# raspi_active_cooling.net
KiCad netlist of a schematic drawn in EAGLE
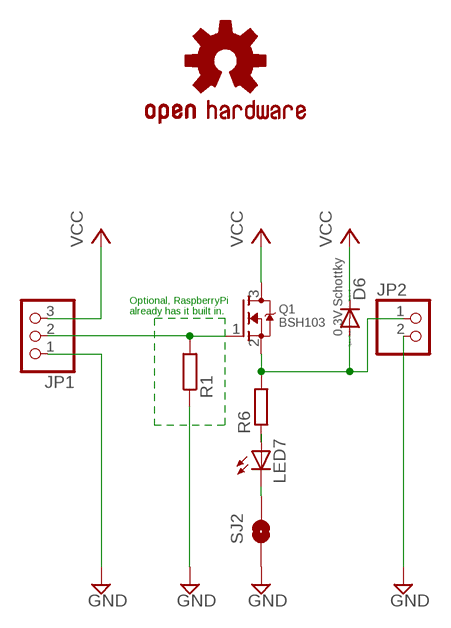
[diagram p0: schematic, sheet 1]

(export (version "E")
  (design (tool "Eeschema 10.0.6"))
  (components
    (comp (ref "D6")
      (value "0.3V Schottky")
      (footprint "eagle-import:SOD523")
      (libsource (lib "eagle-import") (part "DIODE-SOD523"))
    )
    (comp (ref "JP1")
      (value "PINHD-1X3/90")
      (footprint "eagle-import:1X03_90")
      (libsource (lib "eagle-import") (part "PINHD-1X3/90"))
    )
    (comp (ref "JP2")
      (value "PINHD-1X2/90")
      (footprint "eagle-import:1X02_90")
      (libsource (lib "eagle-import") (part "PINHD-1X2/90"))
    )
    (comp (ref "LED7")
      (value "LED0603")
      (footprint "eagle-import:LED-0603")
      (libsource (lib "eagle-import") (part "LED0603"))
    )
    (comp (ref "LOGO1")
      (value "OSHW-LOGOS")
      (footprint "eagle-import:OSHW-LOGO-S")
      (libsource (lib "eagle-import") (part "OSHW-LOGOS"))
    )
    (comp (ref "Q1")
      (value "BSH103")
      (footprint "eagle-import:SOT23")
      (libsource (lib "eagle-import") (part "MOSFET-NREFLOW"))
    )
    (comp (ref "R1")
      (value "R-EU_R0603")
      (footprint "eagle-import:R0603")
      (libsource (lib "eagle-import") (part "R-EU_R0603"))
    )
    (comp (ref "R6")
      (value "R-EU_R0603")
      (footprint "eagle-import:R0603")
      (libsource (lib "eagle-import") (part "R-EU_R0603"))
    )
    (comp (ref "SJ2")
      (value "SOLDERJUMPERNO")
      (footprint "eagle-import:SJ_2S-NO")
      (libsource (lib "eagle-import") (part "SOLDERJUMPERNO"))
    )
  )
  (nets
    (net (code "1") (name "GND") (class "Default")
      (node (ref "JP1") (pin "1") (pinfunction "1_1") (pintype "passive"))
      (node (ref "JP2") (pin "2") (pinfunction "2_2") (pintype "passive"))
      (node (ref "R1") (pin "1") (pinfunction "1_1") (pintype "passive"))
      (node (ref "SJ2") (pin "2") (pinfunction "2_2") (pintype "passive"))
    )
    (net (code "2") (name "Net-(LED7-PadA)") (class "Default")
      (node (ref "LED7") (pin "A") (pinfunction "A_A") (pintype "passive"))
      (node (ref "R6") (pin "1") (pinfunction "1_1") (pintype "passive"))
    )
    (net (code "3") (name "Net-(LED7-PadC)") (class "Default")
      (node (ref "LED7") (pin "C") (pinfunction "C_C") (pintype "passive"))
      (node (ref "SJ2") (pin "1") (pinfunction "1_1") (pintype "passive"))
    )
    (net (code "4") (name "Net-(Q1-G)") (class "Default")
      (node (ref "JP1") (pin "2") (pinfunction "2_2") (pintype "passive"))
      (node (ref "Q1") (pin "1") (pinfunction "G_1") (pintype "bidirectional"))
      (node (ref "R1") (pin "2") (pinfunction "2_2") (pintype "passive"))
    )
    (net (code "5") (name "Net-(Q1-S)") (class "Default")
      (node (ref "D6") (pin "A") (pinfunction "A_A") (pintype "passive"))
      (node (ref "JP2") (pin "1") (pinfunction "1_1") (pintype "passive"))
      (node (ref "Q1") (pin "2") (pinfunction "S_2") (pintype "bidirectional"))
      (node (ref "R6") (pin "2") (pinfunction "2_2") (pintype "passive"))
    )
    (net (code "6") (name "VCC") (class "Default")
      (node (ref "D6") (pin "C") (pinfunction "C_C") (pintype "passive"))
      (node (ref "JP1") (pin "3") (pinfunction "3_3") (pintype "passive"))
      (node (ref "Q1") (pin "3") (pinfunction "D_3") (pintype "bidirectional"))
    )
  )
)
